# SoC_Decoupling_2.net
KiCad netlist of a schematic drawn in Altium Designer
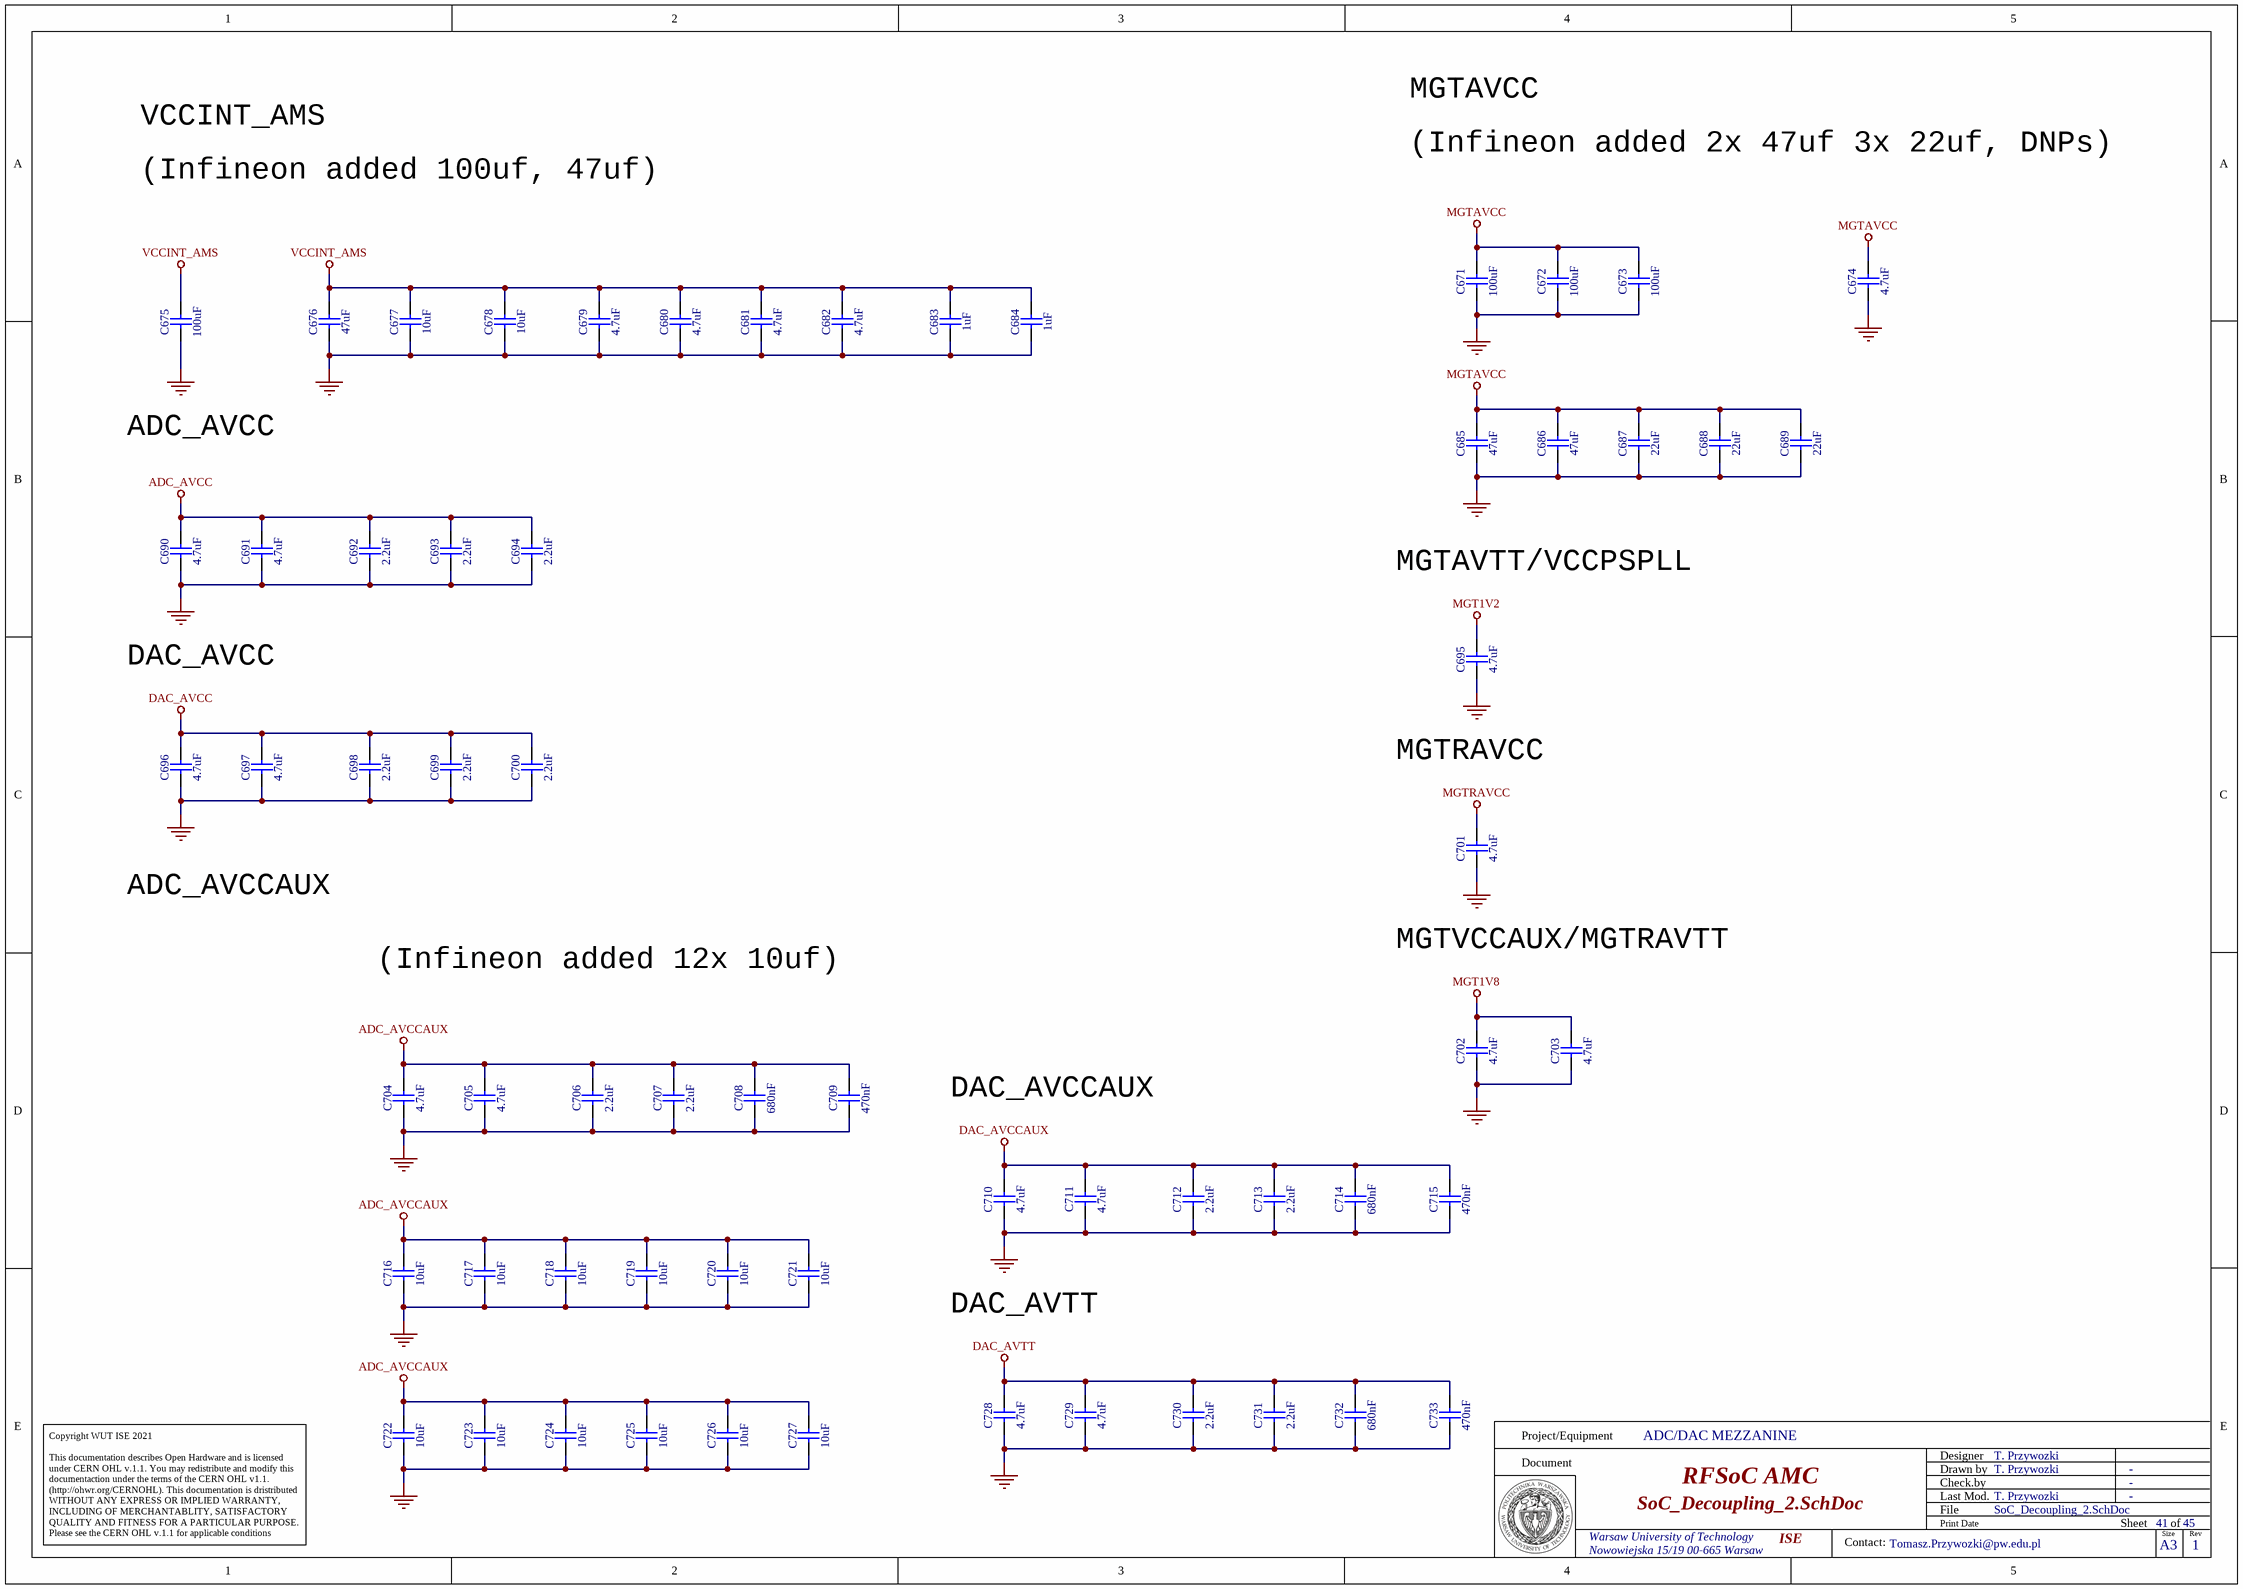
[diagram p0: SoC_Decoupling_2.SchDoc]

(export (version "E")
  (design (tool "Eeschema 10.0.6"))
  (components
    (comp (ref "C671")
      (value "100uF")
      (footprint "CAPC3225X270N")
      (description "Non-polarised capacitor")
      (fields
        (field (name "VOLTAGE") "6.3V")
        (field (name "TOLERANCE") "±20%")
        (field (name "AUTHOR") "CERN DEM JLC")
      )
      (libsource (lib "Capacitors") (part "Capacitor - non polarized"))
    )
    (comp (ref "C672")
      (value "100uF")
      (footprint "CAPC3225X270N")
      (description "Non-polarised capacitor")
      (fields
        (field (name "VOLTAGE") "6.3V")
        (field (name "TOLERANCE") "±20%")
        (field (name "AUTHOR") "CERN DEM JLC")
      )
      (libsource (lib "Capacitors") (part "Capacitor - non polarized"))
    )
    (comp (ref "C673")
      (value "100uF")
      (footprint "CAPC3225X270N")
      (description "Non-polarised capacitor")
      (fields
        (field (name "VOLTAGE") "6.3V")
        (field (name "TOLERANCE") "±20%")
        (field (name "AUTHOR") "CERN DEM JLC")
      )
      (libsource (lib "Capacitors") (part "Capacitor - non polarized"))
    )
    (comp (ref "C674")
      (value "4.7uF")
      (footprint "CAPC1005X55N")
      (description "Non-polarised capacitor")
      (fields
        (field (name "VOLTAGE") "6.3V")
        (field (name "TOLERANCE") "±20%")
        (field (name "AUTHOR") "CERN DEM JLC")
      )
      (libsource (lib "Capacitors") (part "Capacitor - non polarized"))
    )
    (comp (ref "C675")
      (value "100uF")
      (footprint "CAPC3225X270N")
      (description "Non-polarised capacitor")
      (fields
        (field (name "VOLTAGE") "6.3V")
        (field (name "TOLERANCE") "±20%")
        (field (name "AUTHOR") "CERN DEM JLC")
      )
      (libsource (lib "Capacitors") (part "Capacitor - non polarized"))
    )
    (comp (ref "C676")
      (value "47uF")
      (footprint "CAPC1608X100N")
      (description "Non-polarised capacitor")
      (fields
        (field (name "VOLTAGE") "6.3V")
        (field (name "TOLERANCE") "±20%")
        (field (name "AUTHOR") "CERN DEM JLC")
      )
      (libsource (lib "Capacitors") (part "Capacitor - non polarized"))
    )
    (comp (ref "C677")
      (value "10uF")
      (footprint "CAPC1608X80N")
      (description "Non-polarised capacitor")
      (fields
        (field (name "VOLTAGE") "10V")
        (field (name "TOLERANCE") "±10%")
        (field (name "AUTHOR") "CERN DEM JLC")
      )
      (libsource (lib "Capacitors") (part "Capacitor - non polarized"))
    )
    (comp (ref "C678")
      (value "10uF")
      (footprint "CAPC1608X80N")
      (description "Non-polarised capacitor")
      (fields
        (field (name "VOLTAGE") "10V")
        (field (name "TOLERANCE") "±10%")
        (field (name "AUTHOR") "CERN DEM JLC")
      )
      (libsource (lib "Capacitors") (part "Capacitor - non polarized"))
    )
    (comp (ref "C679")
      (value "4.7uF")
      (footprint "CAPC1005X55N")
      (description "Non-polarised capacitor")
      (fields
        (field (name "VOLTAGE") "6.3V")
        (field (name "TOLERANCE") "±20%")
        (field (name "AUTHOR") "CERN DEM JLC")
      )
      (libsource (lib "Capacitors") (part "Capacitor - non polarized"))
    )
    (comp (ref "C680")
      (value "4.7uF")
      (footprint "CAPC1005X55N")
      (description "Non-polarised capacitor")
      (fields
        (field (name "VOLTAGE") "6.3V")
        (field (name "TOLERANCE") "±20%")
        (field (name "AUTHOR") "CERN DEM JLC")
      )
      (libsource (lib "Capacitors") (part "Capacitor - non polarized"))
    )
    (comp (ref "C681")
      (value "4.7uF")
      (footprint "CAPC1005X55N")
      (description "Non-polarised capacitor")
      (fields
        (field (name "VOLTAGE") "6.3V")
        (field (name "TOLERANCE") "±20%")
        (field (name "AUTHOR") "CERN DEM JLC")
      )
      (libsource (lib "Capacitors") (part "Capacitor - non polarized"))
    )
    (comp (ref "C682")
      (value "4.7uF")
      (footprint "CAPC1005X55N")
      (description "Non-polarised capacitor")
      (fields
        (field (name "VOLTAGE") "6.3V")
        (field (name "TOLERANCE") "±20%")
        (field (name "AUTHOR") "CERN DEM JLC")
      )
      (libsource (lib "Capacitors") (part "Capacitor - non polarized"))
    )
    (comp (ref "C683")
      (value "1uF")
      (footprint "CAPC1005X55N")
      (description "Non-polarised capacitor")
      (fields
        (field (name "VOLTAGE") "16V")
        (field (name "TOLERANCE") "±10%")
        (field (name "AUTHOR") "CERN DEM JLC")
      )
      (libsource (lib "Capacitors") (part "Capacitor - non polarized"))
    )
    (comp (ref "C684")
      (value "1uF")
      (footprint "CAPC1005X55N")
      (description "Non-polarised capacitor")
      (fields
        (field (name "VOLTAGE") "16V")
        (field (name "TOLERANCE") "±10%")
        (field (name "AUTHOR") "CERN DEM JLC")
      )
      (libsource (lib "Capacitors") (part "Capacitor - non polarized"))
    )
    (comp (ref "C685")
      (value "47uF")
      (footprint "CAPC1608X100N")
      (description "Non-polarised capacitor")
      (fields
        (field (name "VOLTAGE") "6.3V")
        (field (name "TOLERANCE") "±20%")
        (field (name "AUTHOR") "CERN DEM JLC")
      )
      (libsource (lib "Capacitors") (part "Capacitor - non polarized"))
    )
    (comp (ref "C686")
      (value "47uF")
      (footprint "CAPC1608X100N")
      (description "Non-polarised capacitor")
      (fields
        (field (name "VOLTAGE") "6.3V")
        (field (name "TOLERANCE") "±20%")
        (field (name "AUTHOR") "CERN DEM JLC")
      )
      (libsource (lib "Capacitors") (part "Capacitor - non polarized"))
    )
    (comp (ref "C687")
      (value "22uF")
      (footprint "CAPC3225X270N")
      (description "Non-polarised capacitor")
      (fields
        (field (name "VOLTAGE") "25V")
        (field (name "TOLERANCE") "±10%")
        (field (name "AUTHOR") "CERN DEM JLC")
      )
      (libsource (lib "Capacitors") (part "Capacitor - non polarized"))
    )
    (comp (ref "C688")
      (value "22uF")
      (footprint "CAPC3225X270N")
      (description "Non-polarised capacitor")
      (fields
        (field (name "VOLTAGE") "25V")
        (field (name "TOLERANCE") "±10%")
        (field (name "AUTHOR") "CERN DEM JLC")
      )
      (libsource (lib "Capacitors") (part "Capacitor - non polarized"))
    )
    (comp (ref "C689")
      (value "22uF")
      (footprint "CAPC3225X270N")
      (description "Non-polarised capacitor")
      (fields
        (field (name "VOLTAGE") "25V")
        (field (name "TOLERANCE") "±10%")
        (field (name "AUTHOR") "CERN DEM JLC")
      )
      (libsource (lib "Capacitors") (part "Capacitor - non polarized"))
    )
    (comp (ref "C690")
      (value "4.7uF")
      (footprint "CAPC1005X55N")
      (description "Non-polarised capacitor")
      (fields
        (field (name "VOLTAGE") "6.3V")
        (field (name "TOLERANCE") "±20%")
        (field (name "AUTHOR") "CERN DEM JLC")
      )
      (libsource (lib "Capacitors") (part "Capacitor - non polarized"))
    )
    (comp (ref "C691")
      (value "4.7uF")
      (footprint "CAPC1005X55N")
      (description "Non-polarised capacitor")
      (fields
        (field (name "VOLTAGE") "6.3V")
        (field (name "TOLERANCE") "±20%")
        (field (name "AUTHOR") "CERN DEM JLC")
      )
      (libsource (lib "Capacitors") (part "Capacitor - non polarized"))
    )
    (comp (ref "C692")
      (value "2.2uF")
      (footprint "CAPC1005X55N")
      (description "Non-polarised capacitor")
      (fields
        (field (name "VOLTAGE") "6.3V")
        (field (name "TOLERANCE") "±10%")
        (field (name "AUTHOR") "CERN DEM JMW")
      )
      (libsource (lib "Capacitors") (part "Capacitor - non polarized"))
    )
    (comp (ref "C693")
      (value "2.2uF")
      (footprint "CAPC1005X55N")
      (description "Non-polarised capacitor")
      (fields
        (field (name "VOLTAGE") "6.3V")
        (field (name "TOLERANCE") "±10%")
        (field (name "AUTHOR") "CERN DEM JMW")
      )
      (libsource (lib "Capacitors") (part "Capacitor - non polarized"))
    )
    (comp (ref "C694")
      (value "2.2uF")
      (footprint "CAPC1005X55N")
      (description "Non-polarised capacitor")
      (fields
        (field (name "VOLTAGE") "6.3V")
        (field (name "TOLERANCE") "±10%")
        (field (name "AUTHOR") "CERN DEM JMW")
      )
      (libsource (lib "Capacitors") (part "Capacitor - non polarized"))
    )
    (comp (ref "C695")
      (value "4.7uF")
      (footprint "CAPC1005X55N")
      (description "Non-polarised capacitor")
      (fields
        (field (name "VOLTAGE") "6.3V")
        (field (name "TOLERANCE") "±20%")
        (field (name "AUTHOR") "CERN DEM JLC")
      )
      (libsource (lib "Capacitors") (part "Capacitor - non polarized"))
    )
    (comp (ref "C696")
      (value "4.7uF")
      (footprint "CAPC1005X55N")
      (description "Non-polarised capacitor")
      (fields
        (field (name "VOLTAGE") "6.3V")
        (field (name "TOLERANCE") "±20%")
        (field (name "AUTHOR") "CERN DEM JLC")
      )
      (libsource (lib "Capacitors") (part "Capacitor - non polarized"))
    )
    (comp (ref "C697")
      (value "4.7uF")
      (footprint "CAPC1005X55N")
      (description "Non-polarised capacitor")
      (fields
        (field (name "VOLTAGE") "6.3V")
        (field (name "TOLERANCE") "±20%")
        (field (name "AUTHOR") "CERN DEM JLC")
      )
      (libsource (lib "Capacitors") (part "Capacitor - non polarized"))
    )
    (comp (ref "C698")
      (value "2.2uF")
      (footprint "CAPC1005X55N")
      (description "Non-polarised capacitor")
      (fields
        (field (name "VOLTAGE") "6.3V")
        (field (name "TOLERANCE") "±10%")
        (field (name "AUTHOR") "CERN DEM JMW")
      )
      (libsource (lib "Capacitors") (part "Capacitor - non polarized"))
    )
    (comp (ref "C699")
      (value "2.2uF")
      (footprint "CAPC1005X55N")
      (description "Non-polarised capacitor")
      (fields
        (field (name "VOLTAGE") "6.3V")
        (field (name "TOLERANCE") "±10%")
        (field (name "AUTHOR") "CERN DEM JMW")
      )
      (libsource (lib "Capacitors") (part "Capacitor - non polarized"))
    )
    (comp (ref "C700")
      (value "2.2uF")
      (footprint "CAPC1005X55N")
      (description "Non-polarised capacitor")
      (fields
        (field (name "VOLTAGE") "6.3V")
        (field (name "TOLERANCE") "±10%")
        (field (name "AUTHOR") "CERN DEM JMW")
      )
      (libsource (lib "Capacitors") (part "Capacitor - non polarized"))
    )
    (comp (ref "C701")
      (value "4.7uF")
      (footprint "CAPC1005X55N")
      (description "Non-polarised capacitor")
      (fields
        (field (name "VOLTAGE") "6.3V")
        (field (name "TOLERANCE") "±20%")
        (field (name "AUTHOR") "CERN DEM JLC")
      )
      (libsource (lib "Capacitors") (part "Capacitor - non polarized"))
    )
    (comp (ref "C702")
      (value "4.7uF")
      (footprint "CAPC1005X55N")
      (description "Non-polarised capacitor")
      (fields
        (field (name "VOLTAGE") "6.3V")
        (field (name "TOLERANCE") "±20%")
        (field (name "AUTHOR") "CERN DEM JLC")
      )
      (libsource (lib "Capacitors") (part "Capacitor - non polarized"))
    )
    (comp (ref "C703")
      (value "4.7uF")
      (footprint "CAPC1005X55N")
      (description "Non-polarised capacitor")
      (fields
        (field (name "VOLTAGE") "6.3V")
        (field (name "TOLERANCE") "±20%")
        (field (name "AUTHOR") "CERN DEM JLC")
      )
      (libsource (lib "Capacitors") (part "Capacitor - non polarized"))
    )
    (comp (ref "C704")
      (value "4.7uF")
      (footprint "CAPC1005X55N")
      (description "Non-polarised capacitor")
      (fields
        (field (name "VOLTAGE") "6.3V")
        (field (name "TOLERANCE") "±20%")
        (field (name "AUTHOR") "CERN DEM JLC")
      )
      (libsource (lib "Capacitors") (part "Capacitor - non polarized"))
    )
    (comp (ref "C705")
      (value "4.7uF")
      (footprint "CAPC1005X55N")
      (description "Non-polarised capacitor")
      (fields
        (field (name "VOLTAGE") "6.3V")
        (field (name "TOLERANCE") "±20%")
        (field (name "AUTHOR") "CERN DEM JLC")
      )
      (libsource (lib "Capacitors") (part "Capacitor - non polarized"))
    )
    (comp (ref "C706")
      (value "2.2uF")
      (footprint "CAPC1005X55N")
      (description "Non-polarised capacitor")
      (fields
        (field (name "VOLTAGE") "6.3V")
        (field (name "TOLERANCE") "±10%")
        (field (name "AUTHOR") "CERN DEM JMW")
      )
      (libsource (lib "Capacitors") (part "Capacitor - non polarized"))
    )
    (comp (ref "C707")
      (value "2.2uF")
      (footprint "CAPC1005X55N")
      (description "Non-polarised capacitor")
      (fields
        (field (name "VOLTAGE") "6.3V")
        (field (name "TOLERANCE") "±10%")
        (field (name "AUTHOR") "CERN DEM JMW")
      )
      (libsource (lib "Capacitors") (part "Capacitor - non polarized"))
    )
    (comp (ref "C708")
      (value "680nF")
      (footprint "CAPC1005X55N")
      (description "Non-polarised capacitor")
      (fields
        (field (name "PART NUMBER") "CC0402_680NF_10V_10%_X5R")
        (field (name "VOLTAGE") "10V")
        (field (name "AUTHOR") "CERN DEM BC")
      )
      (libsource (lib "Capacitors") (part "Capacitor - non polarized"))
    )
    (comp (ref "C709")
      (value "470nF")
      (footprint "CAPC1005X55N")
      (description "Non-polarised capacitor")
      (fields
        (field (name "VOLTAGE") "6.3V")
        (field (name "TOLERANCE") "±10%")
        (field (name "AUTHOR") "CERN DEM JLC")
      )
      (libsource (lib "Capacitors") (part "Capacitor - non polarized"))
    )
    (comp (ref "C710")
      (value "4.7uF")
      (footprint "CAPC1005X55N")
      (description "Non-polarised capacitor")
      (fields
        (field (name "VOLTAGE") "6.3V")
        (field (name "TOLERANCE") "±20%")
        (field (name "AUTHOR") "CERN DEM JLC")
      )
      (libsource (lib "Capacitors") (part "Capacitor - non polarized"))
    )
    (comp (ref "C711")
      (value "4.7uF")
      (footprint "CAPC1005X55N")
      (description "Non-polarised capacitor")
      (fields
        (field (name "VOLTAGE") "6.3V")
        (field (name "TOLERANCE") "±20%")
        (field (name "AUTHOR") "CERN DEM JLC")
      )
      (libsource (lib "Capacitors") (part "Capacitor - non polarized"))
    )
    (comp (ref "C712")
      (value "2.2uF")
      (footprint "CAPC1005X55N")
      (description "Non-polarised capacitor")
      (fields
        (field (name "VOLTAGE") "6.3V")
        (field (name "TOLERANCE") "±10%")
        (field (name "AUTHOR") "CERN DEM JMW")
      )
      (libsource (lib "Capacitors") (part "Capacitor - non polarized"))
    )
    (comp (ref "C713")
      (value "2.2uF")
      (footprint "CAPC1005X55N")
      (description "Non-polarised capacitor")
      (fields
        (field (name "VOLTAGE") "6.3V")
        (field (name "TOLERANCE") "±10%")
        (field (name "AUTHOR") "CERN DEM JMW")
      )
      (libsource (lib "Capacitors") (part "Capacitor - non polarized"))
    )
    (comp (ref "C714")
      (value "680nF")
      (footprint "CAPC1005X55N")
      (description "Non-polarised capacitor")
      (fields
        (field (name "PART NUMBER") "CC0402_680NF_10V_10%_X5R")
        (field (name "VOLTAGE") "10V")
        (field (name "AUTHOR") "CERN DEM BC")
      )
      (libsource (lib "Capacitors") (part "Capacitor - non polarized"))
    )
    (comp (ref "C715")
      (value "470nF")
      (footprint "CAPC1005X55N")
      (description "Non-polarised capacitor")
      (fields
        (field (name "VOLTAGE") "6.3V")
        (field (name "TOLERANCE") "±10%")
        (field (name "AUTHOR") "CERN DEM JLC")
      )
      (libsource (lib "Capacitors") (part "Capacitor - non polarized"))
    )
    (comp (ref "C716")
      (value "10uF")
      (footprint "CAPC1608X80N")
      (description "Non-polarised capacitor")
      (fields
        (field (name "VOLTAGE") "10V")
        (field (name "TOLERANCE") "±10%")
        (field (name "AUTHOR") "CERN DEM JLC")
      )
      (libsource (lib "Capacitors") (part "Capacitor - non polarized"))
    )
    (comp (ref "C717")
      (value "10uF")
      (footprint "CAPC1608X80N")
      (description "Non-polarised capacitor")
      (fields
        (field (name "VOLTAGE") "10V")
        (field (name "TOLERANCE") "±10%")
        (field (name "AUTHOR") "CERN DEM JLC")
      )
      (libsource (lib "Capacitors") (part "Capacitor - non polarized"))
    )
    (comp (ref "C718")
      (value "10uF")
      (footprint "CAPC1608X80N")
      (description "Non-polarised capacitor")
      (fields
        (field (name "VOLTAGE") "10V")
        (field (name "TOLERANCE") "±10%")
        (field (name "AUTHOR") "CERN DEM JLC")
      )
      (libsource (lib "Capacitors") (part "Capacitor - non polarized"))
    )
    (comp (ref "C719")
      (value "10uF")
      (footprint "CAPC1608X80N")
      (description "Non-polarised capacitor")
      (fields
        (field (name "VOLTAGE") "10V")
        (field (name "TOLERANCE") "±10%")
        (field (name "AUTHOR") "CERN DEM JLC")
      )
      (libsource (lib "Capacitors") (part "Capacitor - non polarized"))
    )
    (comp (ref "C720")
      (value "10uF")
      (footprint "CAPC1608X80N")
      (description "Non-polarised capacitor")
      (fields
        (field (name "VOLTAGE") "10V")
        (field (name "TOLERANCE") "±10%")
        (field (name "AUTHOR") "CERN DEM JLC")
      )
      (libsource (lib "Capacitors") (part "Capacitor - non polarized"))
    )
    (comp (ref "C721")
      (value "10uF")
      (footprint "CAPC1608X80N")
      (description "Non-polarised capacitor")
      (fields
        (field (name "VOLTAGE") "10V")
        (field (name "TOLERANCE") "±10%")
        (field (name "AUTHOR") "CERN DEM JLC")
      )
      (libsource (lib "Capacitors") (part "Capacitor - non polarized"))
    )
    (comp (ref "C722")
      (value "10uF")
      (footprint "CAPC1608X80N")
      (description "Non-polarised capacitor")
      (fields
        (field (name "VOLTAGE") "10V")
        (field (name "TOLERANCE") "±10%")
        (field (name "AUTHOR") "CERN DEM JLC")
      )
      (libsource (lib "Capacitors") (part "Capacitor - non polarized"))
    )
    (comp (ref "C723")
      (value "10uF")
      (footprint "CAPC1608X80N")
      (description "Non-polarised capacitor")
      (fields
        (field (name "VOLTAGE") "10V")
        (field (name "TOLERANCE") "±10%")
        (field (name "AUTHOR") "CERN DEM JLC")
      )
      (libsource (lib "Capacitors") (part "Capacitor - non polarized"))
    )
    (comp (ref "C724")
      (value "10uF")
      (footprint "CAPC1608X80N")
      (description "Non-polarised capacitor")
      (fields
        (field (name "VOLTAGE") "10V")
        (field (name "TOLERANCE") "±10%")
        (field (name "AUTHOR") "CERN DEM JLC")
      )
      (libsource (lib "Capacitors") (part "Capacitor - non polarized"))
    )
    (comp (ref "C725")
      (value "10uF")
      (footprint "CAPC1608X80N")
      (description "Non-polarised capacitor")
      (fields
        (field (name "VOLTAGE") "10V")
        (field (name "TOLERANCE") "±10%")
        (field (name "AUTHOR") "CERN DEM JLC")
      )
      (libsource (lib "Capacitors") (part "Capacitor - non polarized"))
    )
    (comp (ref "C726")
      (value "10uF")
      (footprint "CAPC1608X80N")
      (description "Non-polarised capacitor")
      (fields
        (field (name "VOLTAGE") "10V")
        (field (name "TOLERANCE") "±10%")
        (field (name "AUTHOR") "CERN DEM JLC")
      )
      (libsource (lib "Capacitors") (part "Capacitor - non polarized"))
    )
    (comp (ref "C727")
      (value "10uF")
      (footprint "CAPC1608X80N")
      (description "Non-polarised capacitor")
      (fields
        (field (name "VOLTAGE") "10V")
        (field (name "TOLERANCE") "±10%")
        (field (name "AUTHOR") "CERN DEM JLC")
      )
      (libsource (lib "Capacitors") (part "Capacitor - non polarized"))
    )
    (comp (ref "C728")
      (value "4.7uF")
      (footprint "CAPC1005X55N")
      (description "Non-polarised capacitor")
      (fields
        (field (name "VOLTAGE") "6.3V")
        (field (name "TOLERANCE") "±20%")
        (field (name "AUTHOR") "CERN DEM JLC")
      )
      (libsource (lib "Capacitors") (part "Capacitor - non polarized"))
    )
    (comp (ref "C729")
      (value "4.7uF")
      (footprint "CAPC1005X55N")
      (description "Non-polarised capacitor")
      (fields
        (field (name "VOLTAGE") "6.3V")
        (field (name "TOLERANCE") "±20%")
        (field (name "AUTHOR") "CERN DEM JLC")
      )
      (libsource (lib "Capacitors") (part "Capacitor - non polarized"))
    )
    (comp (ref "C730")
      (value "2.2uF")
      (footprint "CAPC1005X55N")
      (description "Non-polarised capacitor")
      (fields
        (field (name "VOLTAGE") "6.3V")
        (field (name "TOLERANCE") "±10%")
        (field (name "AUTHOR") "CERN DEM JMW")
      )
      (libsource (lib "Capacitors") (part "Capacitor - non polarized"))
    )
    (comp (ref "C731")
      (value "2.2uF")
      (footprint "CAPC1005X55N")
      (description "Non-polarised capacitor")
      (fields
        (field (name "VOLTAGE") "6.3V")
        (field (name "TOLERANCE") "±10%")
        (field (name "AUTHOR") "CERN DEM JMW")
      )
      (libsource (lib "Capacitors") (part "Capacitor - non polarized"))
    )
    (comp (ref "C732")
      (value "680nF")
      (footprint "CAPC1005X55N")
      (description "Non-polarised capacitor")
      (fields
        (field (name "PART NUMBER") "CC0402_680NF_10V_10%_X5R")
        (field (name "VOLTAGE") "10V")
        (field (name "AUTHOR") "CERN DEM BC")
      )
      (libsource (lib "Capacitors") (part "Capacitor - non polarized"))
    )
    (comp (ref "C733")
      (value "470nF")
      (footprint "CAPC1005X55N")
      (description "Non-polarised capacitor")
      (fields
        (field (name "VOLTAGE") "6.3V")
        (field (name "TOLERANCE") "±10%")
        (field (name "AUTHOR") "CERN DEM JLC")
      )
      (libsource (lib "Capacitors") (part "Capacitor - non polarized"))
    )
  )
  (nets
    (net (code "1") (name "ADC_AVCC") (class "Default")
      (node (ref "C690") (pin "2") (pinfunction "2_2") (pintype "passive"))
      (node (ref "C691") (pin "2") (pinfunction "2_2") (pintype "passive"))
      (node (ref "C692") (pin "2") (pinfunction "2_2") (pintype "passive"))
      (node (ref "C693") (pin "2") (pinfunction "2_2") (pintype "passive"))
      (node (ref "C694") (pin "2") (pinfunction "2_2") (pintype "passive"))
    )
    (net (code "2") (name "ADC_AVCCAUX") (class "Default")
      (node (ref "C704") (pin "2") (pinfunction "2_2") (pintype "passive"))
      (node (ref "C705") (pin "2") (pinfunction "2_2") (pintype "passive"))
      (node (ref "C706") (pin "2") (pinfunction "2_2") (pintype "passive"))
      (node (ref "C707") (pin "2") (pinfunction "2_2") (pintype "passive"))
      (node (ref "C708") (pin "2") (pinfunction "2_2") (pintype "passive"))
      (node (ref "C709") (pin "2") (pinfunction "2_2") (pintype "passive"))
      (node (ref "C716") (pin "2") (pinfunction "2_2") (pintype "passive"))
      (node (ref "C717") (pin "2") (pinfunction "2_2") (pintype "passive"))
      (node (ref "C718") (pin "2") (pinfunction "2_2") (pintype "passive"))
      (node (ref "C719") (pin "2") (pinfunction "2_2") (pintype "passive"))
      (node (ref "C720") (pin "2") (pinfunction "2_2") (pintype "passive"))
      (node (ref "C721") (pin "2") (pinfunction "2_2") (pintype "passive"))
      (node (ref "C722") (pin "2") (pinfunction "2_2") (pintype "passive"))
      (node (ref "C723") (pin "2") (pinfunction "2_2") (pintype "passive"))
      (node (ref "C724") (pin "2") (pinfunction "2_2") (pintype "passive"))
      (node (ref "C725") (pin "2") (pinfunction "2_2") (pintype "passive"))
      (node (ref "C726") (pin "2") (pinfunction "2_2") (pintype "passive"))
      (node (ref "C727") (pin "2") (pinfunction "2_2") (pintype "passive"))
    )
    (net (code "3") (name "DAC_AVCC") (class "Default")
      (node (ref "C696") (pin "2") (pinfunction "2_2") (pintype "passive"))
      (node (ref "C697") (pin "2") (pinfunction "2_2") (pintype "passive"))
      (node (ref "C698") (pin "2") (pinfunction "2_2") (pintype "passive"))
      (node (ref "C699") (pin "2") (pinfunction "2_2") (pintype "passive"))
      (node (ref "C700") (pin "2") (pinfunction "2_2") (pintype "passive"))
    )
    (net (code "4") (name "DAC_AVCCAUX") (class "Default")
      (node (ref "C710") (pin "2") (pinfunction "2_2") (pintype "passive"))
      (node (ref "C711") (pin "2") (pinfunction "2_2") (pintype "passive"))
      (node (ref "C712") (pin "2") (pinfunction "2_2") (pintype "passive"))
      (node (ref "C713") (pin "2") (pinfunction "2_2") (pintype "passive"))
      (node (ref "C714") (pin "2") (pinfunction "2_2") (pintype "passive"))
      (node (ref "C715") (pin "2") (pinfunction "2_2") (pintype "passive"))
    )
    (net (code "5") (name "DAC_AVTT") (class "Default")
      (node (ref "C728") (pin "2") (pinfunction "2_2") (pintype "passive"))
      (node (ref "C729") (pin "2") (pinfunction "2_2") (pintype "passive"))
      (node (ref "C730") (pin "2") (pinfunction "2_2") (pintype "passive"))
      (node (ref "C731") (pin "2") (pinfunction "2_2") (pintype "passive"))
      (node (ref "C732") (pin "2") (pinfunction "2_2") (pintype "passive"))
      (node (ref "C733") (pin "2") (pinfunction "2_2") (pintype "passive"))
    )
    (net (code "6") (name "GND") (class "Default")
      (node (ref "C671") (pin "1") (pinfunction "1_1") (pintype "passive"))
      (node (ref "C672") (pin "1") (pinfunction "1_1") (pintype "passive"))
      (node (ref "C673") (pin "1") (pinfunction "1_1") (pintype "passive"))
      (node (ref "C674") (pin "1") (pinfunction "1_1") (pintype "passive"))
      (node (ref "C675") (pin "1") (pinfunction "1_1") (pintype "passive"))
      (node (ref "C676") (pin "1") (pinfunction "1_1") (pintype "passive"))
      (node (ref "C677") (pin "1") (pinfunction "1_1") (pintype "passive"))
      (node (ref "C678") (pin "1") (pinfunction "1_1") (pintype "passive"))
      (node (ref "C679") (pin "1") (pinfunction "1_1") (pintype "passive"))
      (node (ref "C680") (pin "1") (pinfunction "1_1") (pintype "passive"))
      (node (ref "C681") (pin "1") (pinfunction "1_1") (pintype "passive"))
      (node (ref "C682") (pin "1") (pinfunction "1_1") (pintype "passive"))
      (node (ref "C683") (pin "1") (pinfunction "1_1") (pintype "passive"))
      (node (ref "C684") (pin "1") (pinfunction "1_1") (pintype "passive"))
      (node (ref "C685") (pin "1") (pinfunction "1_1") (pintype "passive"))
      (node (ref "C686") (pin "1") (pinfunction "1_1") (pintype "passive"))
      (node (ref "C687") (pin "1") (pinfunction "1_1") (pintype "passive"))
      (node (ref "C688") (pin "1") (pinfunction "1_1") (pintype "passive"))
      (node (ref "C689") (pin "1") (pinfunction "1_1") (pintype "passive"))
      (node (ref "C690") (pin "1") (pinfunction "1_1") (pintype "passive"))
      (node (ref "C691") (pin "1") (pinfunction "1_1") (pintype "passive"))
      (node (ref "C692") (pin "1") (pinfunction "1_1") (pintype "passive"))
      (node (ref "C693") (pin "1") (pinfunction "1_1") (pintype "passive"))
      (node (ref "C694") (pin "1") (pinfunction "1_1") (pintype "passive"))
      (node (ref "C695") (pin "1") (pinfunction "1_1") (pintype "passive"))
      (node (ref "C696") (pin "1") (pinfunction "1_1") (pintype "passive"))
      (node (ref "C697") (pin "1") (pinfunction "1_1") (pintype "passive"))
      (node (ref "C698") (pin "1") (pinfunction "1_1") (pintype "passive"))
      (node (ref "C699") (pin "1") (pinfunction "1_1") (pintype "passive"))
      (node (ref "C700") (pin "1") (pinfunction "1_1") (pintype "passive"))
      (node (ref "C701") (pin "1") (pinfunction "1_1") (pintype "passive"))
      (node (ref "C702") (pin "1") (pinfunction "1_1") (pintype "passive"))
      (node (ref "C703") (pin "1") (pinfunction "1_1") (pintype "passive"))
      (node (ref "C704") (pin "1") (pinfunction "1_1") (pintype "passive"))
      (node (ref "C705") (pin "1") (pinfunction "1_1") (pintype "passive"))
      (node (ref "C706") (pin "1") (pinfunction "1_1") (pintype "passive"))
      (node (ref "C707") (pin "1") (pinfunction "1_1") (pintype "passive"))
      (node (ref "C708") (pin "1") (pinfunction "1_1") (pintype "passive"))
      (node (ref "C709") (pin "1") (pinfunction "1_1") (pintype "passive"))
      (node (ref "C710") (pin "1") (pinfunction "1_1") (pintype "passive"))
      (node (ref "C711") (pin "1") (pinfunction "1_1") (pintype "passive"))
      (node (ref "C712") (pin "1") (pinfunction "1_1") (pintype "passive"))
      (node (ref "C713") (pin "1") (pinfunction "1_1") (pintype "passive"))
      (node (ref "C714") (pin "1") (pinfunction "1_1") (pintype "passive"))
      (node (ref "C715") (pin "1") (pinfunction "1_1") (pintype "passive"))
      (node (ref "C716") (pin "1") (pinfunction "1_1") (pintype "passive"))
      (node (ref "C717") (pin "1") (pinfunction "1_1") (pintype "passive"))
      (node (ref "C718") (pin "1") (pinfunction "1_1") (pintype "passive"))
      (node (ref "C719") (pin "1") (pinfunction "1_1") (pintype "passive"))
      (node (ref "C720") (pin "1") (pinfunction "1_1") (pintype "passive"))
      (node (ref "C721") (pin "1") (pinfunction "1_1") (pintype "passive"))
      (node (ref "C722") (pin "1") (pinfunction "1_1") (pintype "passive"))
      (node (ref "C723") (pin "1") (pinfunction "1_1") (pintype "passive"))
      (node (ref "C724") (pin "1") (pinfunction "1_1") (pintype "passive"))
      (node (ref "C725") (pin "1") (pinfunction "1_1") (pintype "passive"))
      (node (ref "C726") (pin "1") (pinfunction "1_1") (pintype "passive"))
      (node (ref "C727") (pin "1") (pinfunction "1_1") (pintype "passive"))
      (node (ref "C728") (pin "1") (pinfunction "1_1") (pintype "passive"))
      (node (ref "C729") (pin "1") (pinfunction "1_1") (pintype "passive"))
      (node (ref "C730") (pin "1") (pinfunction "1_1") (pintype "passive"))
      (node (ref "C731") (pin "1") (pinfunction "1_1") (pintype "passive"))
      (node (ref "C732") (pin "1") (pinfunction "1_1") (pintype "passive"))
      (node (ref "C733") (pin "1") (pinfunction "1_1") (pintype "passive"))
    )
    (net (code "7") (name "MGT1V2") (class "Default")
      (node (ref "C695") (pin "2") (pinfunction "2_2") (pintype "passive"))
    )
    (net (code "8") (name "MGT1V8") (class "Default")
      (node (ref "C702") (pin "2") (pinfunction "2_2") (pintype "passive"))
      (node (ref "C703") (pin "2") (pinfunction "2_2") (pintype "passive"))
    )
    (net (code "9") (name "MGTAVCC") (class "Default")
      (node (ref "C671") (pin "2") (pinfunction "2_2") (pintype "passive"))
      (node (ref "C672") (pin "2") (pinfunction "2_2") (pintype "passive"))
      (node (ref "C673") (pin "2") (pinfunction "2_2") (pintype "passive"))
      (node (ref "C674") (pin "2") (pinfunction "2_2") (pintype "passive"))
      (node (ref "C685") (pin "2") (pinfunction "2_2") (pintype "passive"))
      (node (ref "C686") (pin "2") (pinfunction "2_2") (pintype "passive"))
      (node (ref "C687") (pin "2") (pinfunction "2_2") (pintype "passive"))
      (node (ref "C688") (pin "2") (pinfunction "2_2") (pintype "passive"))
      (node (ref "C689") (pin "2") (pinfunction "2_2") (pintype "passive"))
    )
    (net (code "10") (name "MGTRAVCC") (class "Default")
      (node (ref "C701") (pin "2") (pinfunction "2_2") (pintype "passive"))
    )
    (net (code "11") (name "VCCINT_AMS") (class "Default")
      (node (ref "C675") (pin "2") (pinfunction "2_2") (pintype "passive"))
      (node (ref "C676") (pin "2") (pinfunction "2_2") (pintype "passive"))
      (node (ref "C677") (pin "2") (pinfunction "2_2") (pintype "passive"))
      (node (ref "C678") (pin "2") (pinfunction "2_2") (pintype "passive"))
      (node (ref "C679") (pin "2") (pinfunction "2_2") (pintype "passive"))
      (node (ref "C680") (pin "2") (pinfunction "2_2") (pintype "passive"))
      (node (ref "C681") (pin "2") (pinfunction "2_2") (pintype "passive"))
      (node (ref "C682") (pin "2") (pinfunction "2_2") (pintype "passive"))
      (node (ref "C683") (pin "2") (pinfunction "2_2") (pintype "passive"))
      (node (ref "C684") (pin "2") (pinfunction "2_2") (pintype "passive"))
    )
  )
)
